# circuit_etudiant_2025.net
KiCad netlist of a schematic drawn in Altium Designer
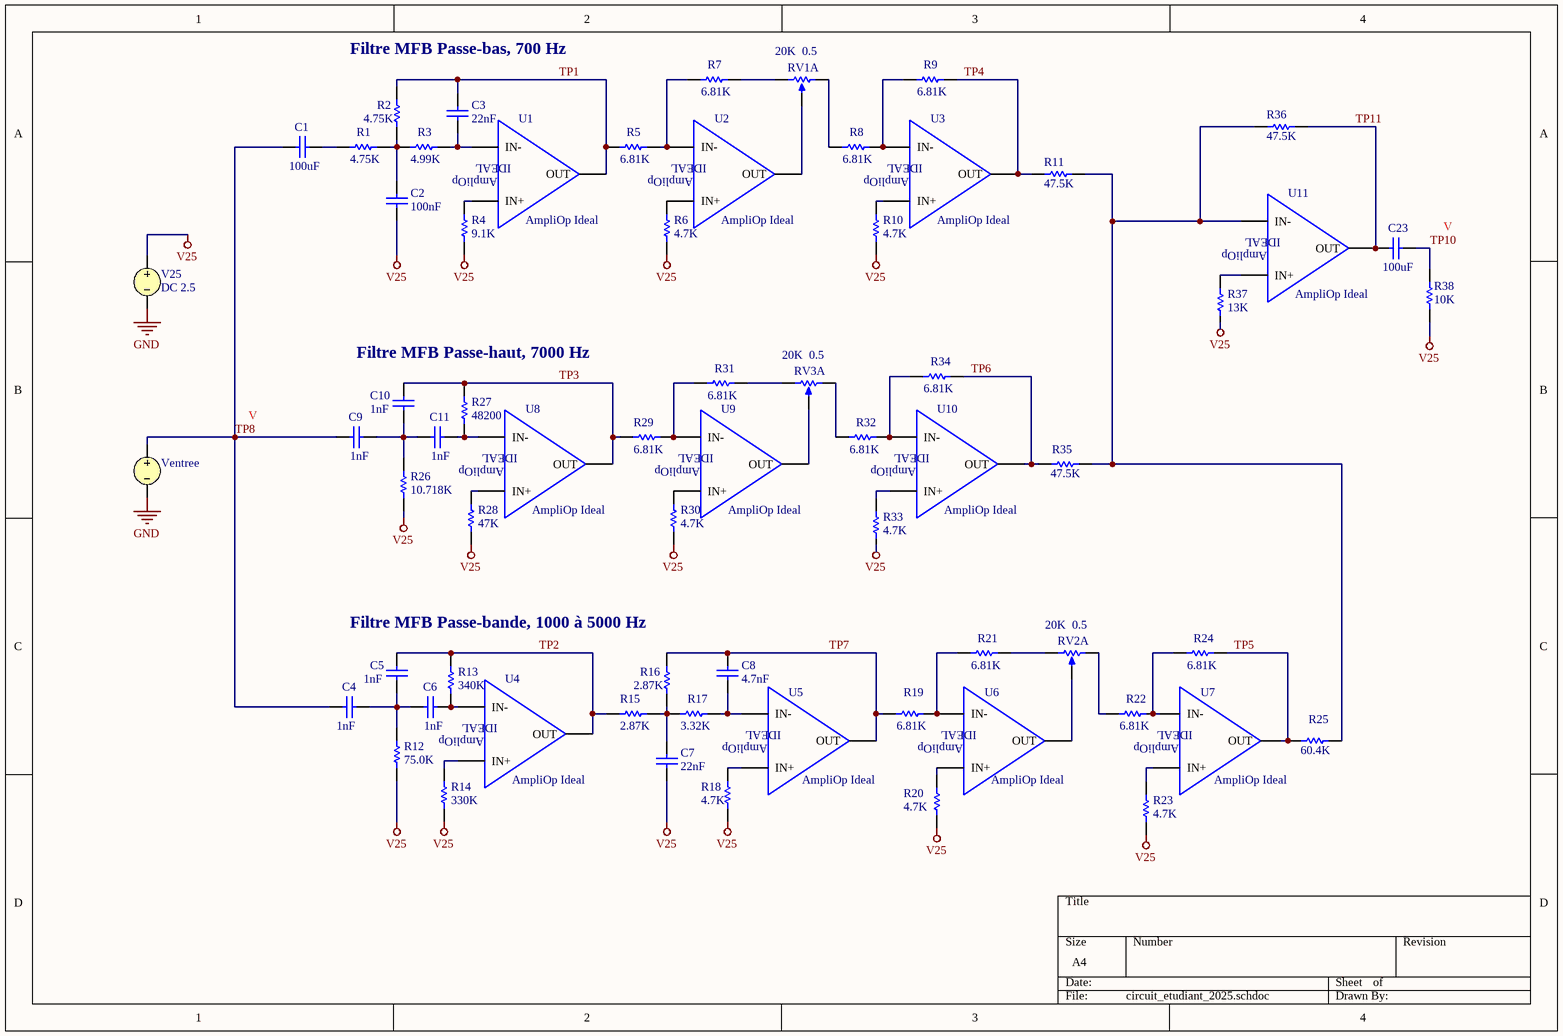
[diagram p0: circuit_etudiant_2025.schdoc]

(export (version "E")
  (design (tool "Eeschema 10.0.6"))
  (components
    (comp (ref "C1")
      (value "100uF")
      (footprint "RAD-0.3")
      (description "Capacitor")
      (fields (field (name "Comment") "Cap") (field (name "PUBLISHER") "Altium Limited"))
      (libsource (lib "Miscellaneous Devices") (part "Cap"))
    )
    (comp (ref "C2")
      (value "100nF")
      (footprint "RAD-0.3")
      (description "Capacitor")
      (fields (field (name "Comment") "Cap") (field (name "PUBLISHER") "Altium Limited"))
      (libsource (lib "Miscellaneous Devices") (part "Cap"))
    )
    (comp (ref "C3")
      (value "22nF")
      (footprint "RAD-0.3")
      (description "Capacitor")
      (fields (field (name "Comment") "Cap") (field (name "PUBLISHER") "Altium Limited"))
      (libsource (lib "Miscellaneous Devices") (part "Cap"))
    )
    (comp (ref "C4")
      (value "1nF")
      (footprint "RAD-0.3")
      (description "Capacitor")
      (fields (field (name "Comment") "Cap") (field (name "PUBLISHER") "Altium Limited"))
      (libsource (lib "Miscellaneous Devices") (part "Cap"))
    )
    (comp (ref "C5")
      (value "1nF")
      (footprint "RAD-0.3")
      (description "Capacitor")
      (fields (field (name "Comment") "Cap") (field (name "PUBLISHER") "Altium Limited"))
      (libsource (lib "Miscellaneous Devices") (part "Cap"))
    )
    (comp (ref "C6")
      (value "1nF")
      (footprint "RAD-0.3")
      (description "Capacitor")
      (fields (field (name "Comment") "Cap") (field (name "PUBLISHER") "Altium Limited"))
      (libsource (lib "Miscellaneous Devices") (part "Cap"))
    )
    (comp (ref "C7")
      (value "22nF")
      (footprint "RAD-0.3")
      (description "Capacitor")
      (fields (field (name "Comment") "Cap") (field (name "PUBLISHER") "Altium Limited"))
      (libsource (lib "Miscellaneous Devices") (part "Cap"))
    )
    (comp (ref "C8")
      (value "4.7nF")
      (footprint "RAD-0.3")
      (description "Capacitor")
      (fields (field (name "Comment") "Cap") (field (name "PUBLISHER") "Altium Limited"))
      (libsource (lib "Miscellaneous Devices") (part "Cap"))
    )
    (comp (ref "C9")
      (value "1nF")
      (footprint "RAD-0.3")
      (description "Capacitor")
      (fields (field (name "Comment") "Cap") (field (name "PUBLISHER") "Altium Limited"))
      (libsource (lib "Miscellaneous Devices") (part "Cap"))
    )
    (comp (ref "C10")
      (value "1nF")
      (footprint "RAD-0.3")
      (description "Capacitor")
      (fields (field (name "Comment") "Cap") (field (name "PUBLISHER") "Altium Limited"))
      (libsource (lib "Miscellaneous Devices") (part "Cap"))
    )
    (comp (ref "C11")
      (value "1nF")
      (footprint "RAD-0.3")
      (description "Capacitor")
      (fields (field (name "Comment") "Cap") (field (name "PUBLISHER") "Altium Limited"))
      (libsource (lib "Miscellaneous Devices") (part "Cap"))
    )
    (comp (ref "C23")
      (value "100uF")
      (footprint "RAD-0.3")
      (description "Capacitor")
      (fields (field (name "Comment") "Cap") (field (name "PUBLISHER") "Altium Limited"))
      (libsource (lib "Miscellaneous Devices") (part "Cap"))
    )
    (comp (ref "R1")
      (value "4.75K")
      (footprint "AXIAL-0.3")
      (description "Resistor")
      (fields (field (name "Comment") "Res1") (field (name "PUBLISHER") "Altium Limited"))
      (libsource (lib "Miscellaneous Devices") (part "Res1"))
    )
    (comp (ref "R2")
      (value "4.75K")
      (footprint "AXIAL-0.3")
      (description "Resistor")
      (fields (field (name "Comment") "Res1") (field (name "PUBLISHER") "Altium Limited"))
      (libsource (lib "Miscellaneous Devices") (part "Res1"))
    )
    (comp (ref "R3")
      (value "4.99K")
      (footprint "AXIAL-0.3")
      (description "Resistor")
      (fields (field (name "Comment") "Res1") (field (name "PUBLISHER") "Altium Limited"))
      (libsource (lib "Miscellaneous Devices") (part "Res1"))
    )
    (comp (ref "R4")
      (value "9.1K")
      (footprint "AXIAL-0.3")
      (description "Resistor")
      (fields (field (name "Comment") "Res1") (field (name "PUBLISHER") "Altium Limited"))
      (libsource (lib "Miscellaneous Devices") (part "Res1"))
    )
    (comp (ref "R5")
      (value "6.81K")
      (footprint "AXIAL-0.3")
      (description "Resistor")
      (fields (field (name "Comment") "Res1") (field (name "PUBLISHER") "Altium Limited"))
      (libsource (lib "Miscellaneous Devices") (part "Res1"))
    )
    (comp (ref "R6")
      (value "4.7K")
      (footprint "AXIAL-0.3")
      (description "Resistor")
      (fields (field (name "Comment") "Res1") (field (name "PUBLISHER") "Altium Limited"))
      (libsource (lib "Miscellaneous Devices") (part "Res1"))
    )
    (comp (ref "R7")
      (value "6.81K")
      (footprint "AXIAL-0.3")
      (description "Resistor")
      (fields (field (name "Comment") "Res1") (field (name "PUBLISHER") "Altium Limited"))
      (libsource (lib "Miscellaneous Devices") (part "Res1"))
    )
    (comp (ref "R8")
      (value "6.81K")
      (footprint "AXIAL-0.3")
      (description "Resistor")
      (fields (field (name "Comment") "Res1") (field (name "PUBLISHER") "Altium Limited"))
      (libsource (lib "Miscellaneous Devices") (part "Res1"))
    )
    (comp (ref "R9")
      (value "6.81K")
      (footprint "AXIAL-0.3")
      (description "Resistor")
      (fields (field (name "Comment") "Res1") (field (name "PUBLISHER") "Altium Limited"))
      (libsource (lib "Miscellaneous Devices") (part "Res1"))
    )
    (comp (ref "R10")
      (value "4.7K")
      (footprint "AXIAL-0.3")
      (description "Resistor")
      (fields (field (name "Comment") "Res1") (field (name "PUBLISHER") "Altium Limited"))
      (libsource (lib "Miscellaneous Devices") (part "Res1"))
    )
    (comp (ref "R11")
      (value "47.5K")
      (footprint "AXIAL-0.3")
      (description "Resistor")
      (fields (field (name "Comment") "Res1") (field (name "PUBLISHER") "Altium Limited"))
      (libsource (lib "Miscellaneous Devices") (part "Res1"))
    )
    (comp (ref "R12")
      (value "75.0K")
      (footprint "AXIAL-0.3")
      (description "Resistor")
      (fields (field (name "Comment") "Res1") (field (name "PUBLISHER") "Altium Limited"))
      (libsource (lib "Miscellaneous Devices") (part "Res1"))
    )
    (comp (ref "R13")
      (value "340K")
      (footprint "AXIAL-0.3")
      (description "Resistor")
      (fields (field (name "Comment") "Res1") (field (name "PUBLISHER") "Altium Limited"))
      (libsource (lib "Miscellaneous Devices") (part "Res1"))
    )
    (comp (ref "R14")
      (value "330K")
      (footprint "AXIAL-0.3")
      (description "Resistor")
      (fields (field (name "Comment") "Res1") (field (name "PUBLISHER") "Altium Limited"))
      (libsource (lib "Miscellaneous Devices") (part "Res1"))
    )
    (comp (ref "R15")
      (value "2.87K")
      (footprint "AXIAL-0.3")
      (description "Resistor")
      (fields (field (name "Comment") "Res1") (field (name "PUBLISHER") "Altium Limited"))
      (libsource (lib "Miscellaneous Devices") (part "Res1"))
    )
    (comp (ref "R16")
      (value "2.87K")
      (footprint "AXIAL-0.3")
      (description "Resistor")
      (fields (field (name "Comment") "Res1") (field (name "PUBLISHER") "Altium Limited"))
      (libsource (lib "Miscellaneous Devices") (part "Res1"))
    )
    (comp (ref "R17")
      (value "3.32K")
      (footprint "AXIAL-0.3")
      (description "Resistor")
      (fields (field (name "Comment") "Res1") (field (name "PUBLISHER") "Altium Limited"))
      (libsource (lib "Miscellaneous Devices") (part "Res1"))
    )
    (comp (ref "R18")
      (value "4.7K")
      (footprint "AXIAL-0.3")
      (description "Resistor")
      (fields (field (name "Comment") "Res1") (field (name "PUBLISHER") "Altium Limited"))
      (libsource (lib "Miscellaneous Devices") (part "Res1"))
    )
    (comp (ref "R19")
      (value "6.81K")
      (footprint "AXIAL-0.3")
      (description "Resistor")
      (fields (field (name "Comment") "Res1") (field (name "PUBLISHER") "Altium Limited"))
      (libsource (lib "Miscellaneous Devices") (part "Res1"))
    )
    (comp (ref "R20")
      (value "4.7K")
      (footprint "AXIAL-0.3")
      (description "Resistor")
      (fields (field (name "Comment") "Res1") (field (name "PUBLISHER") "Altium Limited"))
      (libsource (lib "Miscellaneous Devices") (part "Res1"))
    )
    (comp (ref "R21")
      (value "6.81K")
      (footprint "AXIAL-0.3")
      (description "Resistor")
      (fields (field (name "Comment") "Res1") (field (name "PUBLISHER") "Altium Limited"))
      (libsource (lib "Miscellaneous Devices") (part "Res1"))
    )
    (comp (ref "R22")
      (value "6.81K")
      (footprint "AXIAL-0.3")
      (description "Resistor")
      (fields (field (name "Comment") "Res1") (field (name "PUBLISHER") "Altium Limited"))
      (libsource (lib "Miscellaneous Devices") (part "Res1"))
    )
    (comp (ref "R23")
      (value "4.7K")
      (footprint "AXIAL-0.3")
      (description "Resistor")
      (fields (field (name "Comment") "Res1") (field (name "PUBLISHER") "Altium Limited"))
      (libsource (lib "Miscellaneous Devices") (part "Res1"))
    )
    (comp (ref "R24")
      (value "6.81K")
      (footprint "AXIAL-0.3")
      (description "Resistor")
      (fields (field (name "Comment") "Res1") (field (name "PUBLISHER") "Altium Limited"))
      (libsource (lib "Miscellaneous Devices") (part "Res1"))
    )
    (comp (ref "R25")
      (value "60.4K")
      (footprint "AXIAL-0.3")
      (description "Resistor")
      (fields (field (name "Comment") "Res1") (field (name "PUBLISHER") "Altium Limited"))
      (libsource (lib "Miscellaneous Devices") (part "Res1"))
    )
    (comp (ref "R26")
      (value "10.718K")
      (footprint "AXIAL-0.3")
      (description "Resistor")
      (fields (field (name "Comment") "Res1") (field (name "PUBLISHER") "Altium Limited"))
      (libsource (lib "Miscellaneous Devices") (part "Res1"))
    )
    (comp (ref "R27")
      (value "48200")
      (footprint "AXIAL-0.3")
      (description "Resistor")
      (fields (field (name "Comment") "Res1") (field (name "PUBLISHER") "Altium Limited"))
      (libsource (lib "Miscellaneous Devices") (part "Res1"))
    )
    (comp (ref "R28")
      (value "47K")
      (footprint "AXIAL-0.3")
      (description "Resistor")
      (fields (field (name "Comment") "Res1") (field (name "PUBLISHER") "Altium Limited"))
      (libsource (lib "Miscellaneous Devices") (part "Res1"))
    )
    (comp (ref "R29")
      (value "6.81K")
      (footprint "AXIAL-0.3")
      (description "Resistor")
      (fields (field (name "Comment") "Res1") (field (name "PUBLISHER") "Altium Limited"))
      (libsource (lib "Miscellaneous Devices") (part "Res1"))
    )
    (comp (ref "R30")
      (value "4.7K")
      (footprint "AXIAL-0.3")
      (description "Resistor")
      (fields (field (name "Comment") "Res1") (field (name "PUBLISHER") "Altium Limited"))
      (libsource (lib "Miscellaneous Devices") (part "Res1"))
    )
    (comp (ref "R31")
      (value "6.81K")
      (footprint "AXIAL-0.3")
      (description "Resistor")
      (fields (field (name "Comment") "Res1") (field (name "PUBLISHER") "Altium Limited"))
      (libsource (lib "Miscellaneous Devices") (part "Res1"))
    )
    (comp (ref "R32")
      (value "6.81K")
      (footprint "AXIAL-0.3")
      (description "Resistor")
      (fields (field (name "Comment") "Res1") (field (name "PUBLISHER") "Altium Limited"))
      (libsource (lib "Miscellaneous Devices") (part "Res1"))
    )
    (comp (ref "R33")
      (value "4.7K")
      (footprint "AXIAL-0.3")
      (description "Resistor")
      (fields (field (name "Comment") "Res1") (field (name "PUBLISHER") "Altium Limited"))
      (libsource (lib "Miscellaneous Devices") (part "Res1"))
    )
    (comp (ref "R34")
      (value "6.81K")
      (footprint "AXIAL-0.3")
      (description "Resistor")
      (fields (field (name "Comment") "Res1") (field (name "PUBLISHER") "Altium Limited"))
      (libsource (lib "Miscellaneous Devices") (part "Res1"))
    )
    (comp (ref "R35")
      (value "47.5K")
      (footprint "AXIAL-0.3")
      (description "Resistor")
      (fields (field (name "Comment") "Res1") (field (name "PUBLISHER") "Altium Limited"))
      (libsource (lib "Miscellaneous Devices") (part "Res1"))
    )
    (comp (ref "R36")
      (value "47.5K")
      (footprint "AXIAL-0.3")
      (description "Resistor")
      (fields (field (name "Comment") "Res1") (field (name "PUBLISHER") "Altium Limited"))
      (libsource (lib "Miscellaneous Devices") (part "Res1"))
    )
    (comp (ref "R37")
      (value "13K")
      (footprint "AXIAL-0.3")
      (description "Resistor")
      (fields (field (name "Comment") "Res1") (field (name "PUBLISHER") "Altium Limited"))
      (libsource (lib "Miscellaneous Devices") (part "Res1"))
    )
    (comp (ref "R38")
      (value "10K")
      (footprint "AXIAL-0.3")
      (description "Resistor")
      (fields (field (name "Comment") "Res1") (field (name "PUBLISHER") "Altium Limited"))
      (libsource (lib "Miscellaneous Devices") (part "Res1"))
    )
    (comp (ref "RV1A")
      (value "20K")
      (footprint "VR5")
      (description "Potentiometer")
      (fields
        (field (name "SET POSITION") "0.5")
        (field (name "Comment") "RPot")
        (field (name "PUBLISHER") "Altium Limited")
      )
      (libsource (lib "Miscellaneous Devices") (part "RPot"))
    )
    (comp (ref "RV2A")
      (value "20K")
      (footprint "VR5")
      (description "Potentiometer")
      (fields
        (field (name "SET POSITION") "0.5")
        (field (name "Comment") "RPot")
        (field (name "PUBLISHER") "Altium Limited")
      )
      (libsource (lib "Miscellaneous Devices") (part "RPot"))
    )
    (comp (ref "RV3A")
      (value "20K")
      (footprint "VR5")
      (description "Potentiometer")
      (fields
        (field (name "SET POSITION") "0.5")
        (field (name "Comment") "RPot")
        (field (name "PUBLISHER") "Altium Limited")
      )
      (libsource (lib "Miscellaneous Devices") (part "RPot"))
    )
    (comp (ref "U1") (value "AmpliOp Ideal") (libsource (lib "Librarie_S2") (part "AmpliOp_ideal")))
    (comp (ref "U2") (value "AmpliOp Ideal") (libsource (lib "Librarie_S2") (part "AmpliOp_ideal")))
    (comp (ref "U3") (value "AmpliOp Ideal") (libsource (lib "Librarie_S2") (part "AmpliOp_ideal")))
    (comp (ref "U4") (value "AmpliOp Ideal") (libsource (lib "Librarie_S2") (part "AmpliOp_ideal")))
    (comp (ref "U5") (value "AmpliOp Ideal") (libsource (lib "Librarie_S2") (part "AmpliOp_ideal")))
    (comp (ref "U6") (value "AmpliOp Ideal") (libsource (lib "Librarie_S2") (part "AmpliOp_ideal")))
    (comp (ref "U7") (value "AmpliOp Ideal") (libsource (lib "Librarie_S2") (part "AmpliOp_ideal")))
    (comp (ref "U8") (value "AmpliOp Ideal") (libsource (lib "Librarie_S2") (part "AmpliOp_ideal")))
    (comp (ref "U9") (value "AmpliOp Ideal") (libsource (lib "Librarie_S2") (part "AmpliOp_ideal")))
    (comp (ref "U10") (value "AmpliOp Ideal") (libsource (lib "Librarie_S2") (part "AmpliOp_ideal")))
    (comp (ref "U11") (value "AmpliOp Ideal") (libsource (lib "Librarie_S2") (part "AmpliOp_ideal")))
    (comp (ref "V25")
      (value "DC 2.5")
      (description "Voltage Source")
      (fields (field (name "PUBLISHER") "Altium Limited"))
      (libsource (lib "Simulation Generic Components") (part "VSRC"))
    )
    (comp (ref "Ventree")
      (value "SIN(0 1 1Meg 0 0 0)")
      (description "Voltage Source")
      (fields (field (name "PUBLISHER") "Altium Limited"))
      (libsource (lib "Simulation Generic Components") (part "VSRC"))
    )
  )
  (nets
    (net (code "1") (name "/TP1") (class "Default")
      (node (ref "C3") (pin "1") (pinfunction "1_1") (pintype "passive"))
      (node (ref "R2") (pin "1") (pinfunction "1_1") (pintype "passive"))
      (node (ref "R5") (pin "1") (pinfunction "1_1") (pintype "passive"))
      (node (ref "U1") (pin "3") (pinfunction "OUT_3") (pintype "passive"))
    )
    (net (code "2") (name "/TP2") (class "Default")
      (node (ref "C5") (pin "1") (pinfunction "1_1") (pintype "passive"))
      (node (ref "R13") (pin "1") (pinfunction "1_1") (pintype "passive"))
      (node (ref "R15") (pin "1") (pinfunction "1_1") (pintype "passive"))
      (node (ref "U4") (pin "3") (pinfunction "OUT_3") (pintype "passive"))
    )
    (net (code "3") (name "/TP3") (class "Default")
      (node (ref "C10") (pin "1") (pinfunction "1_1") (pintype "passive"))
      (node (ref "R27") (pin "1") (pinfunction "1_1") (pintype "passive"))
      (node (ref "R29") (pin "1") (pinfunction "1_1") (pintype "passive"))
      (node (ref "U8") (pin "3") (pinfunction "OUT_3") (pintype "passive"))
    )
    (net (code "4") (name "/TP4") (class "Default")
      (node (ref "R11") (pin "1") (pinfunction "1_1") (pintype "passive"))
      (node (ref "R9") (pin "2") (pinfunction "2_2") (pintype "passive"))
      (node (ref "U3") (pin "3") (pinfunction "OUT_3") (pintype "passive"))
    )
    (net (code "5") (name "/TP5") (class "Default")
      (node (ref "R24") (pin "2") (pinfunction "2_2") (pintype "passive"))
      (node (ref "R25") (pin "1") (pinfunction "1_1") (pintype "passive"))
      (node (ref "U7") (pin "3") (pinfunction "OUT_3") (pintype "passive"))
    )
    (net (code "6") (name "/TP6") (class "Default")
      (node (ref "R34") (pin "2") (pinfunction "2_2") (pintype "passive"))
      (node (ref "R35") (pin "1") (pinfunction "1_1") (pintype "passive"))
      (node (ref "U10") (pin "3") (pinfunction "OUT_3") (pintype "passive"))
    )
    (net (code "7") (name "/TP7") (class "Default")
      (node (ref "C8") (pin "1") (pinfunction "1_1") (pintype "passive"))
      (node (ref "R16") (pin "1") (pinfunction "1_1") (pintype "passive"))
      (node (ref "R19") (pin "1") (pinfunction "1_1") (pintype "passive"))
      (node (ref "U5") (pin "3") (pinfunction "OUT_3") (pintype "passive"))
    )
    (net (code "8") (name "/TP8") (class "Default")
      (node (ref "C1") (pin "1") (pinfunction "1_1") (pintype "passive"))
      (node (ref "C4") (pin "1") (pinfunction "1_1") (pintype "passive"))
      (node (ref "C9") (pin "1") (pinfunction "1_1") (pintype "passive"))
      (node (ref "Ventree") (pin "1") (pinfunction "1_1") (pintype "passive"))
    )
    (net (code "9") (name "/TP10") (class "Default")
      (node (ref "C23") (pin "2") (pinfunction "2_2") (pintype "passive"))
      (node (ref "R38") (pin "2") (pinfunction "2_2") (pintype "passive"))
    )
    (net (code "10") (name "/TP11") (class "Default")
      (node (ref "C23") (pin "1") (pinfunction "1_1") (pintype "passive"))
      (node (ref "R36") (pin "2") (pinfunction "2_2") (pintype "passive"))
      (node (ref "U11") (pin "3") (pinfunction "OUT_3") (pintype "passive"))
    )
    (net (code "11") (name "GND") (class "Default")
      (node (ref "V25") (pin "2") (pinfunction "2_2") (pintype "passive"))
      (node (ref "Ventree") (pin "2") (pinfunction "2_2") (pintype "passive"))
    )
    (net (code "12") (name "Net-(C1-Pad2)") (class "Default")
      (node (ref "C1") (pin "2") (pinfunction "2_2") (pintype "passive"))
      (node (ref "R1") (pin "1") (pinfunction "1_1") (pintype "passive"))
    )
    (net (code "13") (name "Net-(C2-Pad1)") (class "Default")
      (node (ref "C2") (pin "1") (pinfunction "1_1") (pintype "passive"))
      (node (ref "R1") (pin "2") (pinfunction "2_2") (pintype "passive"))
      (node (ref "R2") (pin "2") (pinfunction "2_2") (pintype "passive"))
      (node (ref "R3") (pin "1") (pinfunction "1_1") (pintype "passive"))
    )
    (net (code "14") (name "Net-(C4-Pad2)") (class "Default")
      (node (ref "C4") (pin "2") (pinfunction "2_2") (pintype "passive"))
      (node (ref "C5") (pin "2") (pinfunction "2_2") (pintype "passive"))
      (node (ref "C6") (pin "1") (pinfunction "1_1") (pintype "passive"))
      (node (ref "R12") (pin "1") (pinfunction "1_1") (pintype "passive"))
    )
    (net (code "15") (name "Net-(C7-Pad1)") (class "Default")
      (node (ref "C7") (pin "1") (pinfunction "1_1") (pintype "passive"))
      (node (ref "R15") (pin "2") (pinfunction "2_2") (pintype "passive"))
      (node (ref "R16") (pin "2") (pinfunction "2_2") (pintype "passive"))
      (node (ref "R17") (pin "1") (pinfunction "1_1") (pintype "passive"))
    )
    (net (code "16") (name "Net-(C10-Pad2)") (class "Default")
      (node (ref "C10") (pin "2") (pinfunction "2_2") (pintype "passive"))
      (node (ref "C11") (pin "1") (pinfunction "1_1") (pintype "passive"))
      (node (ref "C9") (pin "2") (pinfunction "2_2") (pintype "passive"))
      (node (ref "R26") (pin "1") (pinfunction "1_1") (pintype "passive"))
    )
    (net (code "17") (name "Net-(RV1A-BOT)") (class "Default")
      (node (ref "R8") (pin "1") (pinfunction "1_1") (pintype "passive"))
      (node (ref "RV1A") (pin "2") (pinfunction "BOT_2") (pintype "passive"))
    )
    (net (code "18") (name "Net-(RV1A-TAP)") (class "Default")
      (node (ref "RV1A") (pin "3") (pinfunction "TAP_3") (pintype "passive"))
      (node (ref "U2") (pin "3") (pinfunction "OUT_3") (pintype "passive"))
    )
    (net (code "19") (name "Net-(RV1A-TOP)") (class "Default")
      (node (ref "R7") (pin "2") (pinfunction "2_2") (pintype "passive"))
      (node (ref "RV1A") (pin "1") (pinfunction "TOP_1") (pintype "passive"))
    )
    (net (code "20") (name "Net-(RV2A-BOT)") (class "Default")
      (node (ref "R22") (pin "1") (pinfunction "1_1") (pintype "passive"))
      (node (ref "RV2A") (pin "2") (pinfunction "BOT_2") (pintype "passive"))
    )
    (net (code "21") (name "Net-(RV2A-TAP)") (class "Default")
      (node (ref "RV2A") (pin "3") (pinfunction "TAP_3") (pintype "passive"))
      (node (ref "U6") (pin "3") (pinfunction "OUT_3") (pintype "passive"))
    )
    (net (code "22") (name "Net-(RV2A-TOP)") (class "Default")
      (node (ref "R21") (pin "2") (pinfunction "2_2") (pintype "passive"))
      (node (ref "RV2A") (pin "1") (pinfunction "TOP_1") (pintype "passive"))
    )
    (net (code "23") (name "Net-(RV3A-BOT)") (class "Default")
      (node (ref "R32") (pin "1") (pinfunction "1_1") (pintype "passive"))
      (node (ref "RV3A") (pin "2") (pinfunction "BOT_2") (pintype "passive"))
    )
    (net (code "24") (name "Net-(RV3A-TAP)") (class "Default")
      (node (ref "RV3A") (pin "3") (pinfunction "TAP_3") (pintype "passive"))
      (node (ref "U9") (pin "3") (pinfunction "OUT_3") (pintype "passive"))
    )
    (net (code "25") (name "Net-(RV3A-TOP)") (class "Default")
      (node (ref "R31") (pin "2") (pinfunction "2_2") (pintype "passive"))
      (node (ref "RV3A") (pin "1") (pinfunction "TOP_1") (pintype "passive"))
    )
    (net (code "26") (name "Net-(U1-IN+)") (class "Default")
      (node (ref "R4") (pin "1") (pinfunction "1_1") (pintype "passive"))
      (node (ref "U1") (pin "1") (pinfunction "IN+_1") (pintype "passive"))
    )
    (net (code "27") (name "Net-(U1-IN-)") (class "Default")
      (node (ref "C3") (pin "2") (pinfunction "2_2") (pintype "passive"))
      (node (ref "R3") (pin "2") (pinfunction "2_2") (pintype "passive"))
      (node (ref "U1") (pin "2") (pinfunction "IN-_2") (pintype "passive"))
    )
    (net (code "28") (name "Net-(U2-IN+)") (class "Default")
      (node (ref "R6") (pin "1") (pinfunction "1_1") (pintype "passive"))
      (node (ref "U2") (pin "1") (pinfunction "IN+_1") (pintype "passive"))
    )
    (net (code "29") (name "Net-(U2-IN-)") (class "Default")
      (node (ref "R5") (pin "2") (pinfunction "2_2") (pintype "passive"))
      (node (ref "R7") (pin "1") (pinfunction "1_1") (pintype "passive"))
      (node (ref "U2") (pin "2") (pinfunction "IN-_2") (pintype "passive"))
    )
    (net (code "30") (name "Net-(U3-IN+)") (class "Default")
      (node (ref "R10") (pin "1") (pinfunction "1_1") (pintype "passive"))
      (node (ref "U3") (pin "1") (pinfunction "IN+_1") (pintype "passive"))
    )
    (net (code "31") (name "Net-(U3-IN-)") (class "Default")
      (node (ref "R8") (pin "2") (pinfunction "2_2") (pintype "passive"))
      (node (ref "R9") (pin "1") (pinfunction "1_1") (pintype "passive"))
      (node (ref "U3") (pin "2") (pinfunction "IN-_2") (pintype "passive"))
    )
    (net (code "32") (name "Net-(U4-IN+)") (class "Default")
      (node (ref "R14") (pin "1") (pinfunction "1_1") (pintype "passive"))
      (node (ref "U4") (pin "1") (pinfunction "IN+_1") (pintype "passive"))
    )
    (net (code "33") (name "Net-(U4-IN-)") (class "Default")
      (node (ref "C6") (pin "2") (pinfunction "2_2") (pintype "passive"))
      (node (ref "R13") (pin "2") (pinfunction "2_2") (pintype "passive"))
      (node (ref "U4") (pin "2") (pinfunction "IN-_2") (pintype "passive"))
    )
    (net (code "34") (name "Net-(U5-IN+)") (class "Default")
      (node (ref "R18") (pin "1") (pinfunction "1_1") (pintype "passive"))
      (node (ref "U5") (pin "1") (pinfunction "IN+_1") (pintype "passive"))
    )
    (net (code "35") (name "Net-(U5-IN-)") (class "Default")
      (node (ref "C8") (pin "2") (pinfunction "2_2") (pintype "passive"))
      (node (ref "R17") (pin "2") (pinfunction "2_2") (pintype "passive"))
      (node (ref "U5") (pin "2") (pinfunction "IN-_2") (pintype "passive"))
    )
    (net (code "36") (name "Net-(U6-IN+)") (class "Default")
      (node (ref "R20") (pin "1") (pinfunction "1_1") (pintype "passive"))
      (node (ref "U6") (pin "1") (pinfunction "IN+_1") (pintype "passive"))
    )
    (net (code "37") (name "Net-(U6-IN-)") (class "Default")
      (node (ref "R19") (pin "2") (pinfunction "2_2") (pintype "passive"))
      (node (ref "R21") (pin "1") (pinfunction "1_1") (pintype "passive"))
      (node (ref "U6") (pin "2") (pinfunction "IN-_2") (pintype "passive"))
    )
    (net (code "38") (name "Net-(U7-IN+)") (class "Default")
      (node (ref "R23") (pin "1") (pinfunction "1_1") (pintype "passive"))
      (node (ref "U7") (pin "1") (pinfunction "IN+_1") (pintype "passive"))
    )
    (net (code "39") (name "Net-(U7-IN-)") (class "Default")
      (node (ref "R22") (pin "2") (pinfunction "2_2") (pintype "passive"))
      (node (ref "R24") (pin "1") (pinfunction "1_1") (pintype "passive"))
      (node (ref "U7") (pin "2") (pinfunction "IN-_2") (pintype "passive"))
    )
    (net (code "40") (name "Net-(U8-IN+)") (class "Default")
      (node (ref "R28") (pin "1") (pinfunction "1_1") (pintype "passive"))
      (node (ref "U8") (pin "1") (pinfunction "IN+_1") (pintype "passive"))
    )
    (net (code "41") (name "Net-(U8-IN-)") (class "Default")
      (node (ref "C11") (pin "2") (pinfunction "2_2") (pintype "passive"))
      (node (ref "R27") (pin "2") (pinfunction "2_2") (pintype "passive"))
      (node (ref "U8") (pin "2") (pinfunction "IN-_2") (pintype "passive"))
    )
    (net (code "42") (name "Net-(U9-IN+)") (class "Default")
      (node (ref "R30") (pin "1") (pinfunction "1_1") (pintype "passive"))
      (node (ref "U9") (pin "1") (pinfunction "IN+_1") (pintype "passive"))
    )
    (net (code "43") (name "Net-(U9-IN-)") (class "Default")
      (node (ref "R29") (pin "2") (pinfunction "2_2") (pintype "passive"))
      (node (ref "R31") (pin "1") (pinfunction "1_1") (pintype "passive"))
      (node (ref "U9") (pin "2") (pinfunction "IN-_2") (pintype "passive"))
    )
    (net (code "44") (name "Net-(U10-IN+)") (class "Default")
      (node (ref "R33") (pin "1") (pinfunction "1_1") (pintype "passive"))
      (node (ref "U10") (pin "1") (pinfunction "IN+_1") (pintype "passive"))
    )
    (net (code "45") (name "Net-(U10-IN-)") (class "Default")
      (node (ref "R32") (pin "2") (pinfunction "2_2") (pintype "passive"))
      (node (ref "R34") (pin "1") (pinfunction "1_1") (pintype "passive"))
      (node (ref "U10") (pin "2") (pinfunction "IN-_2") (pintype "passive"))
    )
    (net (code "46") (name "Net-(U11-IN+)") (class "Default")
      (node (ref "R37") (pin "1") (pinfunction "1_1") (pintype "passive"))
      (node (ref "U11") (pin "1") (pinfunction "IN+_1") (pintype "passive"))
    )
    (net (code "47") (name "Net-(U11-IN-)") (class "Default")
      (node (ref "R11") (pin "2") (pinfunction "2_2") (pintype "passive"))
      (node (ref "R25") (pin "2") (pinfunction "2_2") (pintype "passive"))
      (node (ref "R35") (pin "2") (pinfunction "2_2") (pintype "passive"))
      (node (ref "R36") (pin "1") (pinfunction "1_1") (pintype "passive"))
      (node (ref "U11") (pin "2") (pinfunction "IN-_2") (pintype "passive"))
    )
    (net (code "48") (name "V25") (class "Default")
      (node (ref "C2") (pin "2") (pinfunction "2_2") (pintype "passive"))
      (node (ref "C7") (pin "2") (pinfunction "2_2") (pintype "passive"))
      (node (ref "R10") (pin "2") (pinfunction "2_2") (pintype "passive"))
      (node (ref "R12") (pin "2") (pinfunction "2_2") (pintype "passive"))
      (node (ref "R14") (pin "2") (pinfunction "2_2") (pintype "passive"))
      (node (ref "R18") (pin "2") (pinfunction "2_2") (pintype "passive"))
      (node (ref "R20") (pin "2") (pinfunction "2_2") (pintype "passive"))
      (node (ref "R23") (pin "2") (pinfunction "2_2") (pintype "passive"))
      (node (ref "R26") (pin "2") (pinfunction "2_2") (pintype "passive"))
      (node (ref "R28") (pin "2") (pinfunction "2_2") (pintype "passive"))
      (node (ref "R30") (pin "2") (pinfunction "2_2") (pintype "passive"))
      (node (ref "R33") (pin "2") (pinfunction "2_2") (pintype "passive"))
      (node (ref "R37") (pin "2") (pinfunction "2_2") (pintype "passive"))
      (node (ref "R38") (pin "1") (pinfunction "1_1") (pintype "passive"))
      (node (ref "R4") (pin "2") (pinfunction "2_2") (pintype "passive"))
      (node (ref "R6") (pin "2") (pinfunction "2_2") (pintype "passive"))
      (node (ref "V25") (pin "1") (pinfunction "1_1") (pintype "passive"))
    )
  )
)
